# AIO.net
KiCad netlist of a schematic drawn in Altium Designer
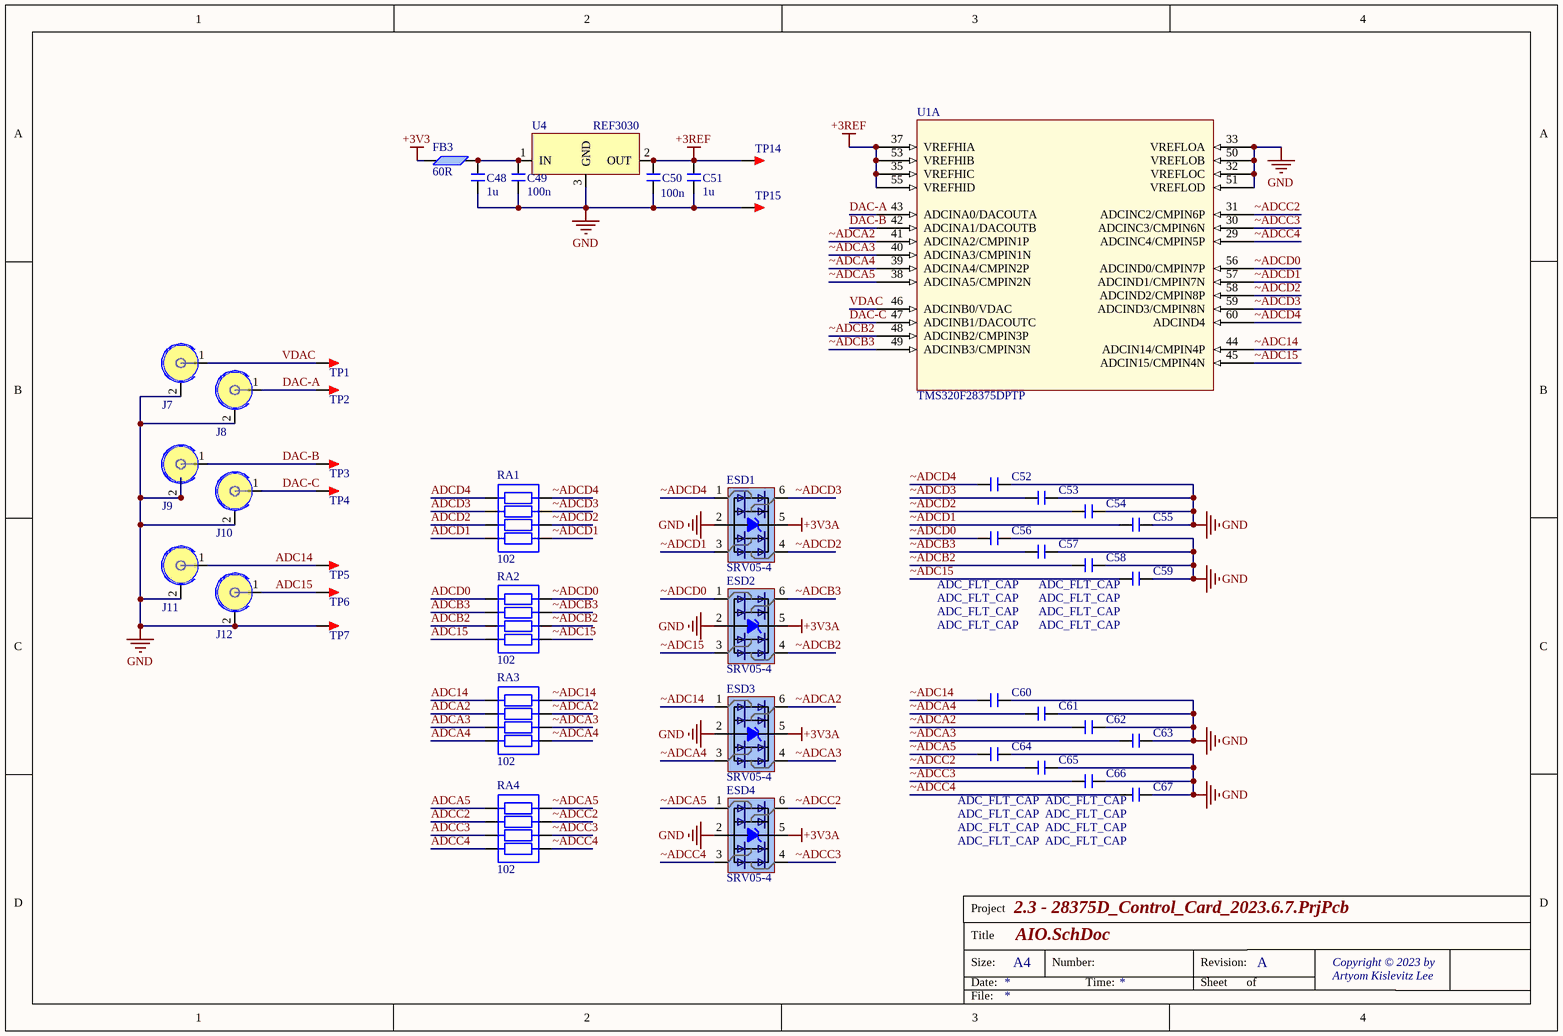
[diagram p0: AIO.SchDoc]

(export (version "E")
  (design (tool "Eeschema 10.0.6"))
  (components
    (comp (ref "C48")
      (value "1u")
      (footprint "C 0805_L")
      (description "贴片电容")
      (libsource (lib "01 - 电容-电阻-电感") (part "C"))
    )
    (comp (ref "C49")
      (value "100n")
      (footprint "C 0805_L")
      (description "贴片电容")
      (libsource (lib "01 - 电容-电阻-电感") (part "C"))
    )
    (comp (ref "C50")
      (value "100n")
      (footprint "C 0805_L")
      (description "贴片电容")
      (libsource (lib "01 - 电容-电阻-电感") (part "C"))
    )
    (comp (ref "C51")
      (value "1u")
      (footprint "C 0805_L")
      (description "贴片电容")
      (libsource (lib "01 - 电容-电阻-电感") (part "C"))
    )
    (comp (ref "C52")
      (value "ADC_FLT_CAP")
      (footprint "C 0805_L")
      (description "贴片电容")
      (libsource (lib "01 - 电容-电阻-电感") (part "C"))
    )
    (comp (ref "C53")
      (value "ADC_FLT_CAP")
      (footprint "C 0805_L")
      (description "贴片电容")
      (libsource (lib "01 - 电容-电阻-电感") (part "C"))
    )
    (comp (ref "C54")
      (value "ADC_FLT_CAP")
      (footprint "C 0805_L")
      (description "贴片电容")
      (libsource (lib "01 - 电容-电阻-电感") (part "C"))
    )
    (comp (ref "C55")
      (value "ADC_FLT_CAP")
      (footprint "C 0805_L")
      (description "贴片电容")
      (libsource (lib "01 - 电容-电阻-电感") (part "C"))
    )
    (comp (ref "C56")
      (value "ADC_FLT_CAP")
      (footprint "C 0805_L")
      (description "贴片电容")
      (libsource (lib "01 - 电容-电阻-电感") (part "C"))
    )
    (comp (ref "C57")
      (value "ADC_FLT_CAP")
      (footprint "C 0805_L")
      (description "贴片电容")
      (libsource (lib "01 - 电容-电阻-电感") (part "C"))
    )
    (comp (ref "C58")
      (value "ADC_FLT_CAP")
      (footprint "C 0805_L")
      (description "贴片电容")
      (libsource (lib "01 - 电容-电阻-电感") (part "C"))
    )
    (comp (ref "C59")
      (value "ADC_FLT_CAP")
      (footprint "C 0805_L")
      (description "贴片电容")
      (libsource (lib "01 - 电容-电阻-电感") (part "C"))
    )
    (comp (ref "C60")
      (value "ADC_FLT_CAP")
      (footprint "C 0805_L")
      (description "贴片电容")
      (libsource (lib "01 - 电容-电阻-电感") (part "C"))
    )
    (comp (ref "C61")
      (value "ADC_FLT_CAP")
      (footprint "C 0805_L")
      (description "贴片电容")
      (libsource (lib "01 - 电容-电阻-电感") (part "C"))
    )
    (comp (ref "C62")
      (value "ADC_FLT_CAP")
      (footprint "C 0805_L")
      (description "贴片电容")
      (libsource (lib "01 - 电容-电阻-电感") (part "C"))
    )
    (comp (ref "C63")
      (value "ADC_FLT_CAP")
      (footprint "C 0805_L")
      (description "贴片电容")
      (libsource (lib "01 - 电容-电阻-电感") (part "C"))
    )
    (comp (ref "C64")
      (value "ADC_FLT_CAP")
      (footprint "C 0805_L")
      (description "贴片电容")
      (libsource (lib "01 - 电容-电阻-电感") (part "C"))
    )
    (comp (ref "C65")
      (value "ADC_FLT_CAP")
      (footprint "C 0805_L")
      (description "贴片电容")
      (libsource (lib "01 - 电容-电阻-电感") (part "C"))
    )
    (comp (ref "C66")
      (value "ADC_FLT_CAP")
      (footprint "C 0805_L")
      (description "贴片电容")
      (libsource (lib "01 - 电容-电阻-电感") (part "C"))
    )
    (comp (ref "C67")
      (value "ADC_FLT_CAP")
      (footprint "C 0805_L")
      (description "贴片电容")
      (libsource (lib "01 - 电容-电阻-电感") (part "C"))
    )
    (comp (ref "ESD1")
      (value "SRV05-4")
      (footprint "SOT23-6L")
      (libsource (lib "02 - 二极管(LED)-三极管-整流桥") (part "ESD - 4"))
    )
    (comp (ref "ESD2")
      (value "SRV05-4")
      (footprint "SOT23-6L")
      (libsource (lib "02 - 二极管(LED)-三极管-整流桥") (part "ESD - 4"))
    )
    (comp (ref "ESD3")
      (value "SRV05-4")
      (footprint "SOT23-6L")
      (libsource (lib "02 - 二极管(LED)-三极管-整流桥") (part "ESD - 4"))
    )
    (comp (ref "ESD4")
      (value "SRV05-4")
      (footprint "SOT23-6L")
      (libsource (lib "02 - 二极管(LED)-三极管-整流桥") (part "ESD - 4"))
    )
    (comp (ref "FB3")
      (value "60R")
      (footprint "R 0805_L")
      (description "磁珠")
      (libsource (lib "01 - 电容-电阻-电感") (part "FB"))
    )
    (comp (ref "J7")
      (value "射频连接器")
      (footprint "IPEX-1")
      (description "射频连接器 RF connector")
      (libsource (lib "43 - 射频") (part "射频连接器"))
    )
    (comp (ref "J8")
      (value "射频连接器")
      (footprint "IPEX-1")
      (description "射频连接器 RF connector")
      (libsource (lib "43 - 射频") (part "射频连接器"))
    )
    (comp (ref "J9")
      (value "射频连接器")
      (footprint "IPEX-1")
      (description "射频连接器 RF connector")
      (libsource (lib "43 - 射频") (part "射频连接器"))
    )
    (comp (ref "J10")
      (value "射频连接器")
      (footprint "IPEX-1")
      (description "射频连接器 RF connector")
      (libsource (lib "43 - 射频") (part "射频连接器"))
    )
    (comp (ref "J11")
      (value "射频连接器")
      (footprint "IPEX-1")
      (description "射频连接器 RF connector")
      (libsource (lib "43 - 射频") (part "射频连接器"))
    )
    (comp (ref "J12")
      (value "射频连接器")
      (footprint "IPEX-1")
      (description "射频连接器 RF connector")
      (libsource (lib "43 - 射频") (part "射频连接器"))
    )
    (comp (ref "RA1")
      (value "102")
      (footprint "RCA-8P4R-0603")
      (description "贴片排阻")
      (libsource (lib "01 - 电容-电阻-电感") (part "R-8P4R"))
    )
    (comp (ref "RA2")
      (value "102")
      (footprint "RCA-8P4R-0603")
      (description "贴片排阻")
      (libsource (lib "01 - 电容-电阻-电感") (part "R-8P4R"))
    )
    (comp (ref "RA3")
      (value "102")
      (footprint "RCA-8P4R-0603")
      (description "贴片排阻")
      (libsource (lib "01 - 电容-电阻-电感") (part "R-8P4R"))
    )
    (comp (ref "RA4")
      (value "102")
      (footprint "RCA-8P4R-0603")
      (description "贴片排阻")
      (libsource (lib "01 - 电容-电阻-电感") (part "R-8P4R"))
    )
    (comp (ref "TP1")
      (value "TEST TP")
      (footprint "TEST TP1.4_W")
      (description "测试环")
      (libsource (lib "10 - 未分类元器件") (part "TEST TP"))
    )
    (comp (ref "TP2")
      (value "TEST TP")
      (footprint "TEST TP1.4_Y")
      (description "测试环")
      (libsource (lib "10 - 未分类元器件") (part "TEST TP"))
    )
    (comp (ref "TP3")
      (value "TEST TP")
      (footprint "TEST TP1.4_Y")
      (description "测试环")
      (libsource (lib "10 - 未分类元器件") (part "TEST TP"))
    )
    (comp (ref "TP4")
      (value "TEST TP")
      (footprint "TEST TP1.4_Y")
      (description "测试环")
      (libsource (lib "10 - 未分类元器件") (part "TEST TP"))
    )
    (comp (ref "TP5")
      (value "TEST TP")
      (footprint "TEST TP1.4_G")
      (description "测试环")
      (libsource (lib "10 - 未分类元器件") (part "TEST TP"))
    )
    (comp (ref "TP6")
      (value "TEST TP")
      (footprint "TEST TP1.4_G")
      (description "测试环")
      (libsource (lib "10 - 未分类元器件") (part "TEST TP"))
    )
    (comp (ref "TP7")
      (value "TEST TP")
      (footprint "TEST TP1.4_B")
      (description "测试环")
      (libsource (lib "10 - 未分类元器件") (part "TEST TP"))
    )
    (comp (ref "TP14")
      (value "TEST")
      (footprint "TEST 1.6")
      (description "测试点")
      (libsource (lib "10 - 未分类元器件") (part "TEST"))
    )
    (comp (ref "TP15")
      (value "TEST")
      (footprint "TEST 1.6")
      (description "测试点")
      (libsource (lib "10 - 未分类元器件") (part "TEST"))
    )
    (comp (ref "U1")
      (value "TMS320F28375DPTP")
      (footprint "LQFP176-E 24x24_N")
      (description "DSP 176")
      (fields
        (field (name "PARTNUMBER") "TMS320F28377DPTP")
        (field (name "MANUFACTURER") "Texas Instruments")
      )
      (libsource (lib "39 - 其他芯片类") (part "TMS320F28377DPTP"))
    )
    (comp (ref "U4") (value "REF3030") (footprint "SOT23-3L") (libsource (lib "08 - 电压基准") (part "REF3030")))
  )
  (nets
    (net (code "1") (name "+3REF") (class "Default")
      (node (ref "C50") (pin "2") (pinfunction "2_2") (pintype "passive"))
      (node (ref "C51") (pin "2") (pinfunction "2_2") (pintype "passive"))
      (node (ref "TP14") (pin "1") (pinfunction "1_1") (pintype "passive"))
      (node (ref "U1") (pin "35") (pinfunction "VREFHIC_35") (pintype "input"))
      (node (ref "U1") (pin "37") (pinfunction "VREFHIA_37") (pintype "input"))
      (node (ref "U1") (pin "53") (pinfunction "VREFHIB_53") (pintype "input"))
      (node (ref "U1") (pin "55") (pinfunction "VREFHID_55") (pintype "input"))
      (node (ref "U4") (pin "2") (pinfunction "OUT_2") (pintype "passive"))
    )
    (net (code "2") (name "+3V3") (class "Default")
      (node (ref "FB3") (pin "1") (pinfunction "1_1") (pintype "passive"))
    )
    (net (code "3") (name "+3V3A") (class "Default")
      (node (ref "ESD1") (pin "5") (pinfunction "EPAD_5") (pintype "passive"))
      (node (ref "ESD2") (pin "5") (pinfunction "EPAD_5") (pintype "passive"))
      (node (ref "ESD3") (pin "5") (pinfunction "EPAD_5") (pintype "passive"))
      (node (ref "ESD4") (pin "5") (pinfunction "EPAD_5") (pintype "passive"))
    )
    (net (code "4") (name "/ADC14") (class "Default")
      (node (ref "J11") (pin "1") (pinfunction "SIG_1") (pintype "passive"))
      (node (ref "RA3") (pin "8") (pinfunction "8_8") (pintype "passive"))
      (node (ref "TP5") (pin "1") (pinfunction "1_1") (pintype "passive"))
    )
    (net (code "5") (name "/ADC15") (class "Default")
      (node (ref "J12") (pin "1") (pinfunction "SIG_1") (pintype "passive"))
      (node (ref "RA2") (pin "5") (pinfunction "5_5") (pintype "passive"))
      (node (ref "TP6") (pin "1") (pinfunction "1_1") (pintype "passive"))
    )
    (net (code "6") (name "/ADCA2") (class "Default")
      (node (ref "RA3") (pin "7") (pinfunction "7_7") (pintype "passive"))
    )
    (net (code "7") (name "/ADCA3") (class "Default")
      (node (ref "RA3") (pin "6") (pinfunction "6_6") (pintype "passive"))
    )
    (net (code "8") (name "/ADCA4") (class "Default")
      (node (ref "RA3") (pin "5") (pinfunction "5_5") (pintype "passive"))
    )
    (net (code "9") (name "/ADCA5") (class "Default")
      (node (ref "RA4") (pin "8") (pinfunction "8_8") (pintype "passive"))
    )
    (net (code "10") (name "/ADCB2") (class "Default")
      (node (ref "RA2") (pin "6") (pinfunction "6_6") (pintype "passive"))
    )
    (net (code "11") (name "/ADCB3") (class "Default")
      (node (ref "RA2") (pin "7") (pinfunction "7_7") (pintype "passive"))
    )
    (net (code "12") (name "/ADCC2") (class "Default")
      (node (ref "RA4") (pin "7") (pinfunction "7_7") (pintype "passive"))
    )
    (net (code "13") (name "/ADCC3") (class "Default")
      (node (ref "RA4") (pin "6") (pinfunction "6_6") (pintype "passive"))
    )
    (net (code "14") (name "/ADCC4") (class "Default")
      (node (ref "RA4") (pin "5") (pinfunction "5_5") (pintype "passive"))
    )
    (net (code "15") (name "/ADCD0") (class "Default")
      (node (ref "RA2") (pin "8") (pinfunction "8_8") (pintype "passive"))
    )
    (net (code "16") (name "/ADCD1") (class "Default")
      (node (ref "RA1") (pin "5") (pinfunction "5_5") (pintype "passive"))
    )
    (net (code "17") (name "/ADCD2") (class "Default")
      (node (ref "RA1") (pin "6") (pinfunction "6_6") (pintype "passive"))
    )
    (net (code "18") (name "/ADCD3") (class "Default")
      (node (ref "RA1") (pin "7") (pinfunction "7_7") (pintype "passive"))
    )
    (net (code "19") (name "/ADCD4") (class "Default")
      (node (ref "RA1") (pin "8") (pinfunction "8_8") (pintype "passive"))
    )
    (net (code "20") (name "/DAC-A") (class "Default")
      (node (ref "J8") (pin "1") (pinfunction "SIG_1") (pintype "passive"))
      (node (ref "TP2") (pin "1") (pinfunction "1_1") (pintype "passive"))
      (node (ref "U1") (pin "43") (pinfunction "ADCINA0/DACOUTA_43") (pintype "input"))
    )
    (net (code "21") (name "/DAC-B") (class "Default")
      (node (ref "J9") (pin "1") (pinfunction "SIG_1") (pintype "passive"))
      (node (ref "TP3") (pin "1") (pinfunction "1_1") (pintype "passive"))
      (node (ref "U1") (pin "42") (pinfunction "ADCINA1/DACOUTB_42") (pintype "input"))
    )
    (net (code "22") (name "/DAC-C") (class "Default")
      (node (ref "J10") (pin "1") (pinfunction "SIG_1") (pintype "passive"))
      (node (ref "TP4") (pin "1") (pinfunction "1_1") (pintype "passive"))
      (node (ref "U1") (pin "47") (pinfunction "ADCINB1/DACOUTC_47") (pintype "input"))
    )
    (net (code "23") (name "/VDAC") (class "Default")
      (node (ref "J7") (pin "1") (pinfunction "SIG_1") (pintype "passive"))
      (node (ref "TP1") (pin "1") (pinfunction "1_1") (pintype "passive"))
      (node (ref "U1") (pin "46") (pinfunction "ADCINB0/VDAC_46") (pintype "input"))
    )
    (net (code "24") (name "/~ADC14") (class "Default")
      (node (ref "C60") (pin "2") (pinfunction "2_2") (pintype "passive"))
      (node (ref "ESD3") (pin "1") (pinfunction "EPAD_1") (pintype "passive"))
      (node (ref "RA3") (pin "1") (pinfunction "1_1") (pintype "passive"))
      (node (ref "U1") (pin "44") (pinfunction "ADCIN14/CMPIN4P_44") (pintype "input"))
    )
    (net (code "25") (name "/~ADC15") (class "Default")
      (node (ref "C59") (pin "2") (pinfunction "2_2") (pintype "passive"))
      (node (ref "ESD2") (pin "3") (pinfunction "EPAD_3") (pintype "passive"))
      (node (ref "RA2") (pin "4") (pinfunction "4_4") (pintype "passive"))
      (node (ref "U1") (pin "45") (pinfunction "ADCIN15/CMPIN4N_45") (pintype "input"))
    )
    (net (code "26") (name "/~ADCA2") (class "Default")
      (node (ref "C62") (pin "2") (pinfunction "2_2") (pintype "passive"))
      (node (ref "ESD3") (pin "6") (pinfunction "EPAD_6") (pintype "passive"))
      (node (ref "RA3") (pin "2") (pinfunction "2_2") (pintype "passive"))
      (node (ref "U1") (pin "41") (pinfunction "ADCINA2/CMPIN1P_41") (pintype "input"))
    )
    (net (code "27") (name "/~ADCA3") (class "Default")
      (node (ref "C63") (pin "2") (pinfunction "2_2") (pintype "passive"))
      (node (ref "ESD3") (pin "4") (pinfunction "EPAD_4") (pintype "passive"))
      (node (ref "RA3") (pin "3") (pinfunction "3_3") (pintype "passive"))
      (node (ref "U1") (pin "40") (pinfunction "ADCINA3/CMPIN1N_40") (pintype "input"))
    )
    (net (code "28") (name "/~ADCA4") (class "Default")
      (node (ref "C61") (pin "2") (pinfunction "2_2") (pintype "passive"))
      (node (ref "ESD3") (pin "3") (pinfunction "EPAD_3") (pintype "passive"))
      (node (ref "RA3") (pin "4") (pinfunction "4_4") (pintype "passive"))
      (node (ref "U1") (pin "39") (pinfunction "ADCINA4/CMPIN2P_39") (pintype "input"))
    )
    (net (code "29") (name "/~ADCA5") (class "Default")
      (node (ref "C64") (pin "2") (pinfunction "2_2") (pintype "passive"))
      (node (ref "ESD4") (pin "1") (pinfunction "EPAD_1") (pintype "passive"))
      (node (ref "RA4") (pin "1") (pinfunction "1_1") (pintype "passive"))
      (node (ref "U1") (pin "38") (pinfunction "ADCINA5/CMPIN2N_38") (pintype "input"))
    )
    (net (code "30") (name "/~ADCB2") (class "Default")
      (node (ref "C58") (pin "2") (pinfunction "2_2") (pintype "passive"))
      (node (ref "ESD2") (pin "4") (pinfunction "EPAD_4") (pintype "passive"))
      (node (ref "RA2") (pin "3") (pinfunction "3_3") (pintype "passive"))
      (node (ref "U1") (pin "48") (pinfunction "ADCINB2/CMPIN3P_48") (pintype "input"))
    )
    (net (code "31") (name "/~ADCB3") (class "Default")
      (node (ref "C57") (pin "2") (pinfunction "2_2") (pintype "passive"))
      (node (ref "ESD2") (pin "6") (pinfunction "EPAD_6") (pintype "passive"))
      (node (ref "RA2") (pin "2") (pinfunction "2_2") (pintype "passive"))
      (node (ref "U1") (pin "49") (pinfunction "ADCINB3/CMPIN3N_49") (pintype "input"))
    )
    (net (code "32") (name "/~ADCC2") (class "Default")
      (node (ref "C65") (pin "2") (pinfunction "2_2") (pintype "passive"))
      (node (ref "ESD4") (pin "6") (pinfunction "EPAD_6") (pintype "passive"))
      (node (ref "RA4") (pin "2") (pinfunction "2_2") (pintype "passive"))
      (node (ref "U1") (pin "31") (pinfunction "ADCINC2/CMPIN6P_31") (pintype "input"))
    )
    (net (code "33") (name "/~ADCC3") (class "Default")
      (node (ref "C66") (pin "2") (pinfunction "2_2") (pintype "passive"))
      (node (ref "ESD4") (pin "4") (pinfunction "EPAD_4") (pintype "passive"))
      (node (ref "RA4") (pin "3") (pinfunction "3_3") (pintype "passive"))
      (node (ref "U1") (pin "30") (pinfunction "ADCINC3/CMPIN6N_30") (pintype "input"))
    )
    (net (code "34") (name "/~ADCC4") (class "Default")
      (node (ref "C67") (pin "2") (pinfunction "2_2") (pintype "passive"))
      (node (ref "ESD4") (pin "3") (pinfunction "EPAD_3") (pintype "passive"))
      (node (ref "RA4") (pin "4") (pinfunction "4_4") (pintype "passive"))
      (node (ref "U1") (pin "29") (pinfunction "ADCINC4/CMPIN5P_29") (pintype "input"))
    )
    (net (code "35") (name "/~ADCD0") (class "Default")
      (node (ref "C56") (pin "2") (pinfunction "2_2") (pintype "passive"))
      (node (ref "ESD2") (pin "1") (pinfunction "EPAD_1") (pintype "passive"))
      (node (ref "RA2") (pin "1") (pinfunction "1_1") (pintype "passive"))
      (node (ref "U1") (pin "56") (pinfunction "ADCIND0/CMPIN7P_56") (pintype "input"))
    )
    (net (code "36") (name "/~ADCD1") (class "Default")
      (node (ref "C55") (pin "2") (pinfunction "2_2") (pintype "passive"))
      (node (ref "ESD1") (pin "3") (pinfunction "EPAD_3") (pintype "passive"))
      (node (ref "RA1") (pin "4") (pinfunction "4_4") (pintype "passive"))
      (node (ref "U1") (pin "57") (pinfunction "ADCIND1/CMPIN7N_57") (pintype "input"))
    )
    (net (code "37") (name "/~ADCD2") (class "Default")
      (node (ref "C54") (pin "2") (pinfunction "2_2") (pintype "passive"))
      (node (ref "ESD1") (pin "4") (pinfunction "EPAD_4") (pintype "passive"))
      (node (ref "RA1") (pin "3") (pinfunction "3_3") (pintype "passive"))
      (node (ref "U1") (pin "58") (pinfunction "ADCIND2/CMPIN8P_58") (pintype "input"))
    )
    (net (code "38") (name "/~ADCD3") (class "Default")
      (node (ref "C53") (pin "2") (pinfunction "2_2") (pintype "passive"))
      (node (ref "ESD1") (pin "6") (pinfunction "EPAD_6") (pintype "passive"))
      (node (ref "RA1") (pin "2") (pinfunction "2_2") (pintype "passive"))
      (node (ref "U1") (pin "59") (pinfunction "ADCIND3/CMPIN8N_59") (pintype "input"))
    )
    (net (code "39") (name "/~ADCD4") (class "Default")
      (node (ref "C52") (pin "2") (pinfunction "2_2") (pintype "passive"))
      (node (ref "ESD1") (pin "1") (pinfunction "EPAD_1") (pintype "passive"))
      (node (ref "RA1") (pin "1") (pinfunction "1_1") (pintype "passive"))
      (node (ref "U1") (pin "60") (pinfunction "ADCIND4_60") (pintype "input"))
    )
    (net (code "40") (name "GND") (class "Default")
      (node (ref "C48") (pin "1") (pinfunction "1_1") (pintype "passive"))
      (node (ref "C49") (pin "1") (pinfunction "1_1") (pintype "passive"))
      (node (ref "C50") (pin "1") (pinfunction "1_1") (pintype "passive"))
      (node (ref "C51") (pin "1") (pinfunction "1_1") (pintype "passive"))
      (node (ref "C52") (pin "1") (pinfunction "1_1") (pintype "passive"))
      (node (ref "C53") (pin "1") (pinfunction "1_1") (pintype "passive"))
      (node (ref "C54") (pin "1") (pinfunction "1_1") (pintype "passive"))
      (node (ref "C55") (pin "1") (pinfunction "1_1") (pintype "passive"))
      (node (ref "C56") (pin "1") (pinfunction "1_1") (pintype "passive"))
      (node (ref "C57") (pin "1") (pinfunction "1_1") (pintype "passive"))
      (node (ref "C58") (pin "1") (pinfunction "1_1") (pintype "passive"))
      (node (ref "C59") (pin "1") (pinfunction "1_1") (pintype "passive"))
      (node (ref "C60") (pin "1") (pinfunction "1_1") (pintype "passive"))
      (node (ref "C61") (pin "1") (pinfunction "1_1") (pintype "passive"))
      (node (ref "C62") (pin "1") (pinfunction "1_1") (pintype "passive"))
      (node (ref "C63") (pin "1") (pinfunction "1_1") (pintype "passive"))
      (node (ref "C64") (pin "1") (pinfunction "1_1") (pintype "passive"))
      (node (ref "C65") (pin "1") (pinfunction "1_1") (pintype "passive"))
      (node (ref "C66") (pin "1") (pinfunction "1_1") (pintype "passive"))
      (node (ref "C67") (pin "1") (pinfunction "1_1") (pintype "passive"))
      (node (ref "ESD1") (pin "2") (pinfunction "EPAD_2") (pintype "passive"))
      (node (ref "ESD2") (pin "2") (pinfunction "EPAD_2") (pintype "passive"))
      (node (ref "ESD3") (pin "2") (pinfunction "EPAD_2") (pintype "passive"))
      (node (ref "ESD4") (pin "2") (pinfunction "EPAD_2") (pintype "passive"))
      (node (ref "J10") (pin "2") (pinfunction "GND_2") (pintype "passive"))
      (node (ref "J11") (pin "2") (pinfunction "GND_2") (pintype "passive"))
      (node (ref "J12") (pin "2") (pinfunction "GND_2") (pintype "passive"))
      (node (ref "J7") (pin "2") (pinfunction "GND_2") (pintype "passive"))
      (node (ref "J8") (pin "2") (pinfunction "GND_2") (pintype "passive"))
      (node (ref "J9") (pin "2") (pinfunction "GND_2") (pintype "passive"))
      (node (ref "TP15") (pin "1") (pinfunction "1_1") (pintype "passive"))
      (node (ref "TP7") (pin "1") (pinfunction "1_1") (pintype "passive"))
      (node (ref "U1") (pin "32") (pinfunction "VREFLOC_32") (pintype "input"))
      (node (ref "U1") (pin "33") (pinfunction "VREFLOA_33") (pintype "input"))
      (node (ref "U1") (pin "50") (pinfunction "VREFLOB_50") (pintype "input"))
      (node (ref "U1") (pin "51") (pinfunction "VREFLOD_51") (pintype "input"))
      (node (ref "U4") (pin "3") (pinfunction "GND_3") (pintype "passive"))
    )
    (net (code "41") (name "Net-(U4-IN)") (class "Default")
      (node (ref "C48") (pin "2") (pinfunction "2_2") (pintype "passive"))
      (node (ref "C49") (pin "2") (pinfunction "2_2") (pintype "passive"))
      (node (ref "FB3") (pin "2") (pinfunction "2_2") (pintype "passive"))
      (node (ref "U4") (pin "1") (pinfunction "IN_1") (pintype "passive"))
    )
  )
)
